# Board_Power.net
KiCad netlist of a schematic drawn in Altium Designer
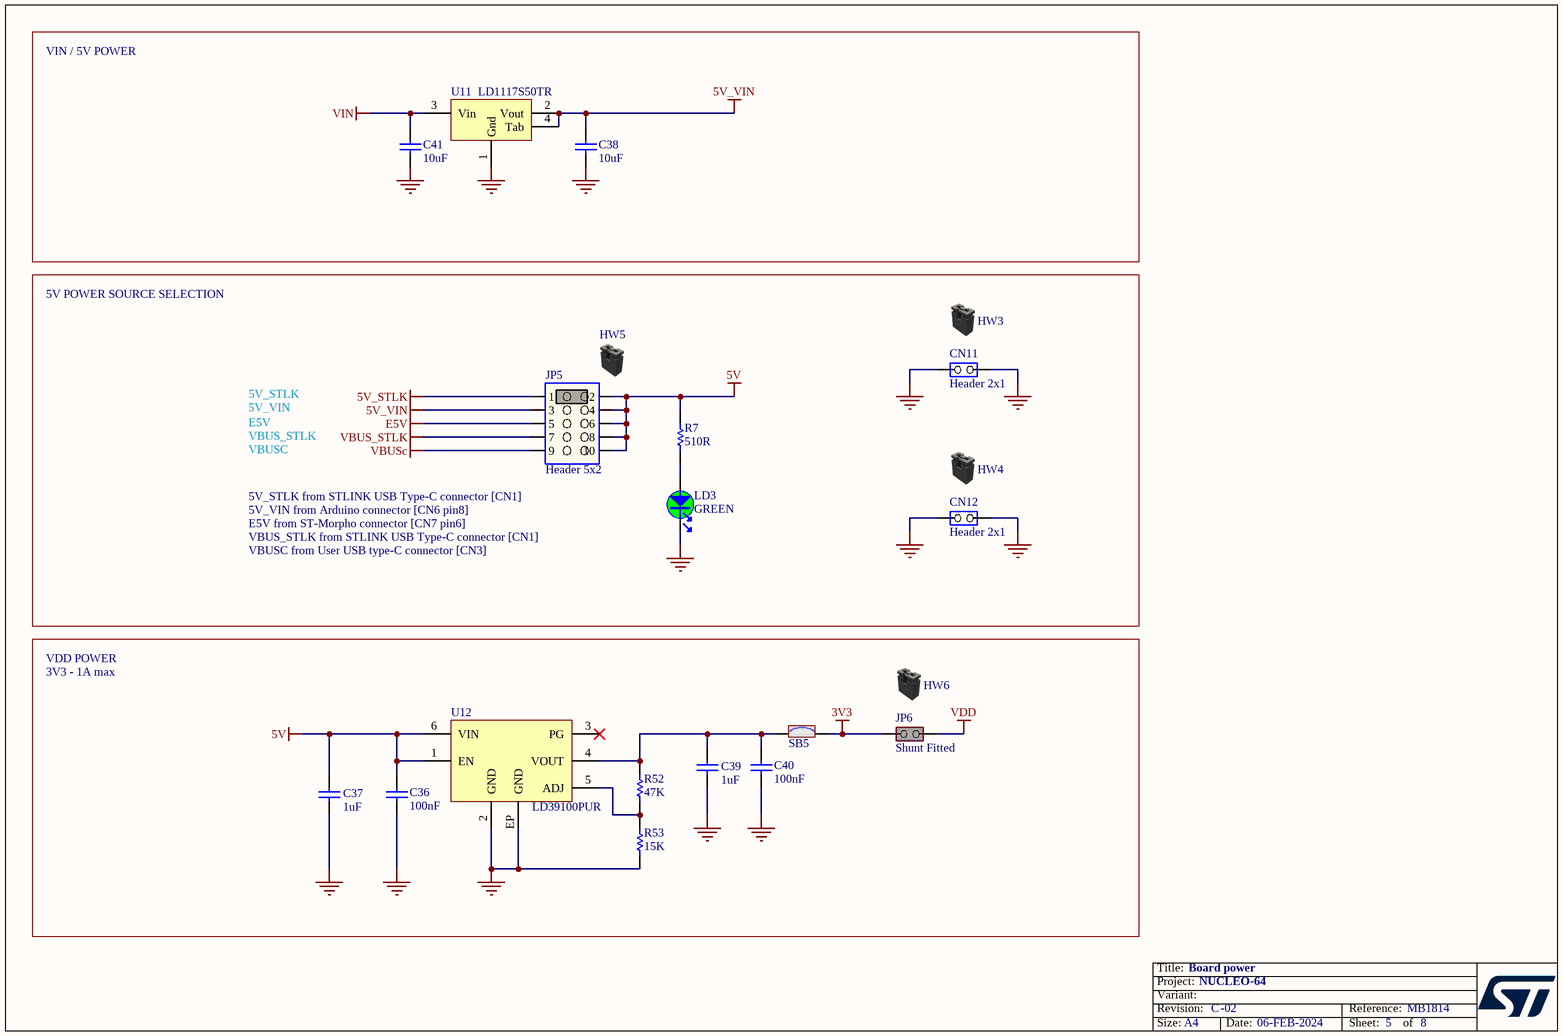
[diagram p0: Board_Power.SchDoc]

(export (version "E")
  (design (tool "Eeschema 10.0.6"))
  (components
    (comp (ref "C36")
      (value "100nF")
      (footprint "C0402")
      (description "Capacitor, MLCC, 100nF, 16V, X7R, +/-10%, 0402, T=0.5mm")
      (fields (field (name "INTERNAL_PART_NUMBER") "MCD-00006") (field (name "MANUFACTURER") "YAGEO"))
      (libsource (lib "MCD_PARTS_database") (part "Capacitor"))
    )
    (comp (ref "C37")
      (value "1uF")
      (footprint "C0603")
      (description "Capacitor, MLCC, 1uF, 16V, X5R, 10%, 0603, T=0,8mm")
      (fields
        (field (name "INTERNAL_PART_NUMBER") "MCD-00010")
        (field (name "MANUFACTURER_PART_NUMBER") "CC0603KRX5R7BB105")
        (field (name "PROVIDED_BY") "Subcon")
      )
      (libsource (lib "MCD_PARTS_database") (part "Capacitor"))
    )
    (comp (ref "C38")
      (value "10uF")
      (footprint "C0805")
      (description "Capacitor, MLCC, 10uF, 25V, X5R, 10%, 0805, T=0,85mm")
      (fields
        (field (name "INTERNAL_PART_NUMBER") "MCD-00014")
        (field (name "MANUFACTURER_PART_NUMBER") "CC0805KRX5R8BB106")
        (field (name "PROVIDED_BY") "SUBCO")
      )
      (libsource (lib "MCD_PARTS_database") (part "Capacitor"))
    )
    (comp (ref "C39")
      (value "1uF")
      (footprint "C0603")
      (description "Capacitor, MLCC, 1uF, 16V, X5R, 10%, 0603, T=0,8mm")
      (fields
        (field (name "INTERNAL_PART_NUMBER") "MCD-00010")
        (field (name "MANUFACTURER_PART_NUMBER") "CC0603KRX5R7BB105")
        (field (name "PROVIDED_BY") "Subcon")
      )
      (libsource (lib "MCD_PARTS_database") (part "Capacitor"))
    )
    (comp (ref "C40")
      (value "100nF")
      (footprint "C0402")
      (description "Capacitor, MLCC, 100nF, 16V, X7R, +/-10%, 0402, T=0.5mm")
      (fields (field (name "INTERNAL_PART_NUMBER") "MCD-00006") (field (name "MANUFACTURER") "YAGEO"))
      (libsource (lib "MCD_PARTS_database") (part "Capacitor"))
    )
    (comp (ref "C41")
      (value "10uF")
      (footprint "C0805")
      (description "Capacitor, MLCC, 10uF, 25V, X5R, 10%, 0805, T=0,85mm")
      (fields
        (field (name "INTERNAL_PART_NUMBER") "MCD-00014")
        (field (name "MANUFACTURER_PART_NUMBER") "CC0805KRX5R8BB106")
        (field (name "PROVIDED_BY") "SUBCO")
      )
      (libsource (lib "MCD_PARTS_database") (part "Capacitor"))
    )
    (comp (ref "CN11")
      (value "Header 2x1")
      (footprint "CON_SAMTEC_TSW-102-09-X-S")
      (description "Header, 2x1, 2.54mm, VR, TH, T=5.84mm/10.16mm")
      (fields (field (name "INTERNAL_PART_NUMBER") "MCD-00214") (field (name "MANUFACTURER") "SAMTEC"))
      (libsource (lib "MCD_PARTS_database") (part "Jumper_Header 2x1"))
    )
    (comp (ref "CN12")
      (value "Header 2x1")
      (footprint "CON_SAMTEC_TSW-102-09-X-S")
      (description "Header, 2x1, 2.54mm, VR, TH, T=5.84mm/10.16mm")
      (fields (field (name "INTERNAL_PART_NUMBER") "MCD-00214") (field (name "MANUFACTURER") "SAMTEC"))
      (libsource (lib "MCD_PARTS_database") (part "Jumper_Header 2x1"))
    )
    (comp (ref "HW3")
      (value "~")
      (description "SHUNT 2.54mm BLACK")
      (fields
        (field (name "INTERNAL_PART_NUMBER") "MCD-00043")
        (field (name "MANUFACTURER_PART_NUMBER") "SNT-100-BK-G")
        (field (name "PROVIDED_BY") "Subcon")
      )
      (libsource (lib "MCD_PARTS_database") (part "Shunt Black 2.54mm"))
    )
    (comp (ref "HW4")
      (value "~")
      (description "SHUNT 2.54mm BLACK")
      (fields
        (field (name "INTERNAL_PART_NUMBER") "MCD-00043")
        (field (name "MANUFACTURER_PART_NUMBER") "SNT-100-BK-G")
        (field (name "PROVIDED_BY") "Subcon")
      )
      (libsource (lib "MCD_PARTS_database") (part "Shunt Black 2.54mm"))
    )
    (comp (ref "HW5")
      (value "~")
      (description "SHUNT 2.54mm BLACK")
      (fields
        (field (name "INTERNAL_PART_NUMBER") "MCD-00043")
        (field (name "MANUFACTURER_PART_NUMBER") "SNT-100-BK-G")
        (field (name "PROVIDED_BY") "Subcon")
      )
      (libsource (lib "MCD_PARTS_database") (part "Shunt Black 2.54mm"))
    )
    (comp (ref "HW6")
      (value "~")
      (description "SHUNT 2.54mm BLACK")
      (fields
        (field (name "INTERNAL_PART_NUMBER") "MCD-00043")
        (field (name "MANUFACTURER_PART_NUMBER") "SNT-100-BK-G")
        (field (name "PROVIDED_BY") "Subcon")
      )
      (libsource (lib "MCD_PARTS_database") (part "Shunt Black 2.54mm"))
    )
    (comp (ref "JP5")
      (value "Header 5x2")
      (footprint "CON_SAMTEC_TSW-105-07-X-D")
      (description "Header, 5x2, 2.54mm, VR, TH, T=5.84mm/2.54mm")
      (fields (field (name "INTERNAL_PART_NUMBER") "MCD-01203") (field (name "BMS_PART_NUMBER") "9083523"))
      (libsource (lib "MCD_PARTS_database") (part "Jumper_Header 5x2 Fitted 1-2"))
    )
    (comp (ref "JP6")
      (value "Shunt Fitted")
      (footprint "CON_SAMTEC_TSW-102-07-G-S")
      (description "Header, 2x1, 2,54mm, VR, TH, Height 5.84mm/2.54mm - Shunt Fitted by default")
      (fields
        (field (name "INTERNAL_PART_NUMBER") "MCD-00683")
        (field (name "MANUFACTURER_PART_NUMBER") "TSW-102-07-x-S")
        (field (name "PROVIDED_BY") "Subcon")
      )
      (libsource (lib "MCD_PARTS_database") (part "Jumper_Header 2x1 Fitted"))
    )
    (comp (ref "LD3")
      (value "GREEN")
      (footprint "LED_0603_OSRAM_LG-Q396-PS-35_GREEN_1A2K_H0P4")
      (description "LED Green, 0603 SMD, Forward Voltage Typ=2V, Max=2.5V")
      (fields
        (field (name "INTERNAL_PART_NUMBER") "MCD-00588")
        (field (name "MANUFACTURER_PART_NUMBER") "LG Q396-PS-35")
        (field (name "PROVIDED_BY") "SUBCO")
      )
      (libsource (lib "MCD_PARTS_database") (part "LED_green"))
    )
    (comp (ref "R7")
      (value "510R")
      (footprint "R0603")
      (description "Resistor,510R,0603,1%,1/10W")
      (fields
        (field (name "INTERNAL_PART_NUMBER") "MCD-00225")
        (field (name "MANUFACTURER_PART_NUMBER") "RC0603FR-07510RL")
        (field (name "PROVIDED_BY") "SUBCO")
      )
      (libsource (lib "MCD_PARTS_database") (part "Resistor"))
    )
    (comp (ref "R52")
      (value "47K")
      (footprint "R0402")
      (description "Resistor, 47K, 0402, +/-1%, 1/16W")
      (fields (field (name "INTERNAL_PART_NUMBER") "MCD-00063") (field (name "MANUFACTURER") "YAGEO"))
      (libsource (lib "MCD_PARTS_database") (part "Resistor"))
    )
    (comp (ref "R53")
      (value "15K")
      (footprint "R0402")
      (description "Resistor, 15K, 0402, +/-1%, 1/16W")
      (fields (field (name "INTERNAL_PART_NUMBER") "MCD-01943") (field (name "MANUFACTURER") "YAGEO"))
      (libsource (lib "MCD_PARTS_database") (part "Resistor"))
    )
    (comp (ref "SB5")
      (value "~")
      (footprint "SOLDER-BRIDGE_R0603-0R")
      (description "Solder Bridge ON")
      (fields
        (field (name "INTERNAL_PART_NUMBER") "MCD-00071")
        (field (name "MANUFACTURER_PART_NUMBER") "RC0603JR-070RL")
        (field (name "PROVIDED_BY") "SUBCO")
      )
      (libsource (lib "MCD_PARTS_database") (part "SB_ON"))
    )
    (comp (ref "U11")
      (value "LD1117S50TR")
      (footprint "REG_SOT223-TAB")
      (description "IC REG LDO 5V 0.8A SOT223")
      (fields
        (field (name "INTERNAL_PART_NUMBER") "MCD-00088")
        (field (name "MANUFACTURER") "STMICROELECTRONICS")
        (field (name "PROVIDED_BY") "SUBCO with ST control")
      )
      (libsource (lib "MCD_PARTS_database") (part "LD1117S50TR"))
    )
    (comp (ref "U12")
      (value "LD39100PUR")
      (footprint "ICC_DFN6-EPAD_3X3_P095")
      (description "LDO, 1V5 to 5V5V, 1A adjustable")
      (fields
        (field (name "INTERNAL_PART_NUMBER") "MCD-03339")
        (field (name "MANUFACTURER") "STMICROELECTRONICS")
      )
      (libsource (lib "MCD_PARTS_database") (part "LD39100PUR"))
    )
  )
  (nets
    (net (code "1") (name "3V3") (class "Default")
      (node (ref "JP6") (pin "1") (pinfunction "COMMON_1") (pintype "passive"))
      (node (ref "SB5") (pin "2") (pinfunction "2_2") (pintype "passive"))
    )
    (net (code "2") (name "5V") (class "Default")
      (node (ref "C36") (pin "2") (pinfunction "2_2") (pintype "passive"))
      (node (ref "C37") (pin "2") (pinfunction "2_2") (pintype "passive"))
      (node (ref "JP5") (pin "10") (pinfunction "10_10") (pintype "passive"))
      (node (ref "JP5") (pin "2") (pinfunction "2_2") (pintype "passive"))
      (node (ref "JP5") (pin "4") (pinfunction "4_4") (pintype "passive"))
      (node (ref "JP5") (pin "6") (pinfunction "6_6") (pintype "passive"))
      (node (ref "JP5") (pin "8") (pinfunction "8_8") (pintype "passive"))
      (node (ref "R7") (pin "2") (pinfunction "2_2") (pintype "passive"))
      (node (ref "U12") (pin "1") (pinfunction "EN_1") (pintype "passive"))
      (node (ref "U12") (pin "6") (pinfunction "VIN_6") (pintype "passive"))
    )
    (net (code "3") (name "5V_STLK") (class "Default")
      (node (ref "JP5") (pin "1") (pinfunction "1_1") (pintype "passive"))
    )
    (net (code "4") (name "5V_VIN") (class "Default")
      (node (ref "C38") (pin "2") (pinfunction "2_2") (pintype "passive"))
      (node (ref "JP5") (pin "3") (pinfunction "3_3") (pintype "passive"))
      (node (ref "U11") (pin "2") (pinfunction "Vout_2") (pintype "passive"))
      (node (ref "U11") (pin "4") (pinfunction "Tab_4") (pintype "passive"))
    )
    (net (code "5") (name "E5V") (class "Default")
      (node (ref "JP5") (pin "5") (pinfunction "5_5") (pintype "passive"))
    )
    (net (code "6") (name "GND") (class "Default")
      (node (ref "C36") (pin "1") (pinfunction "1_1") (pintype "passive"))
      (node (ref "C37") (pin "1") (pinfunction "1_1") (pintype "passive"))
      (node (ref "C38") (pin "1") (pinfunction "1_1") (pintype "passive"))
      (node (ref "C39") (pin "1") (pinfunction "1_1") (pintype "passive"))
      (node (ref "C40") (pin "1") (pinfunction "1_1") (pintype "passive"))
      (node (ref "C41") (pin "1") (pinfunction "1_1") (pintype "passive"))
      (node (ref "CN11") (pin "1") (pinfunction "COMMON_1") (pintype "passive"))
      (node (ref "CN11") (pin "2") (pinfunction "NO_2") (pintype "passive"))
      (node (ref "CN12") (pin "1") (pinfunction "COMMON_1") (pintype "passive"))
      (node (ref "CN12") (pin "2") (pinfunction "NO_2") (pintype "passive"))
      (node (ref "LD3") (pin "2") (pintype "passive"))
      (node (ref "R53") (pin "1") (pinfunction "1_1") (pintype "passive"))
      (node (ref "U11") (pin "1") (pinfunction "Gnd_1") (pintype "passive"))
      (node (ref "U12") (pin "2") (pinfunction "GND_2") (pintype "passive"))
      (node (ref "U12") (pin "EP") (pinfunction "GND_EP") (pintype "passive"))
    )
    (net (code "7") (name "Net-(LD3-Pad1)") (class "Default")
      (node (ref "LD3") (pin "1") (pintype "passive"))
      (node (ref "R7") (pin "1") (pinfunction "1_1") (pintype "passive"))
    )
    (net (code "8") (name "Net-(U12-ADJ)") (class "Default")
      (node (ref "R52") (pin "1") (pinfunction "1_1") (pintype "passive"))
      (node (ref "R53") (pin "2") (pinfunction "2_2") (pintype "passive"))
      (node (ref "U12") (pin "5") (pinfunction "ADJ_5") (pintype "passive"))
    )
    (net (code "9") (name "Net-(U12-VOUT)") (class "Default")
      (node (ref "C39") (pin "2") (pinfunction "2_2") (pintype "passive"))
      (node (ref "C40") (pin "2") (pinfunction "2_2") (pintype "passive"))
      (node (ref "R52") (pin "2") (pinfunction "2_2") (pintype "passive"))
      (node (ref "SB5") (pin "1") (pinfunction "1_1") (pintype "passive"))
      (node (ref "U12") (pin "4") (pinfunction "VOUT_4") (pintype "passive"))
    )
    (net (code "10") (name "VBUS_STLK") (class "Default")
      (node (ref "JP5") (pin "7") (pinfunction "7_7") (pintype "passive"))
    )
    (net (code "11") (name "VBUSc") (class "Default")
      (node (ref "JP5") (pin "9") (pinfunction "9_9") (pintype "passive"))
    )
    (net (code "12") (name "VDD") (class "Default")
      (node (ref "JP6") (pin "2") (pinfunction "NO_2") (pintype "passive"))
    )
    (net (code "13") (name "VIN") (class "Default")
      (node (ref "C41") (pin "2") (pinfunction "2_2") (pintype "passive"))
      (node (ref "U11") (pin "3") (pinfunction "Vin_3") (pintype "passive"))
    )
    (net (code "14") (name "unconnected-(U12-PG-Pad3)") (class "Default")
      (node (ref "U12") (pin "3") (pinfunction "PG_3") (pintype "passive+no_connect"))
    )
  )
)
